# harger_for_auto_2.net
KiCad netlist of a schematic drawn in Altium Designer
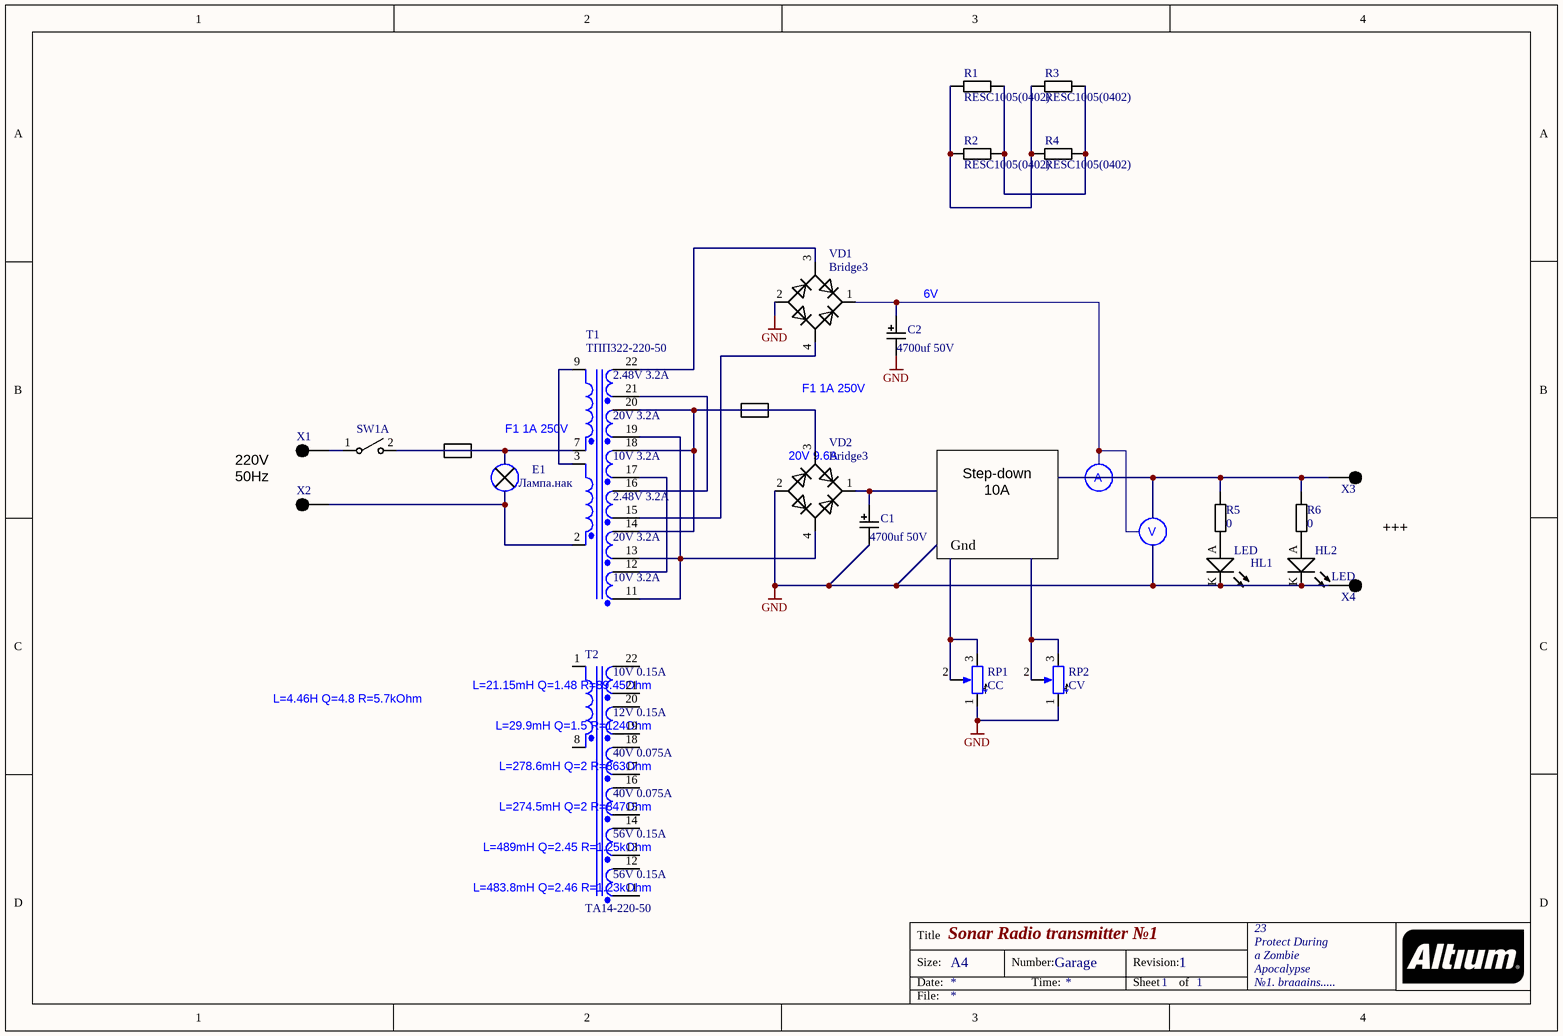
[diagram p0: Сharger for auto (2).SchDoc]

(export (version "E")
  (design (tool "Eeschema 10.0.6"))
  (components
    (comp (ref "C1")
      (value "4700uf 50V")
      (footprint "CAPMP3528X210N")
      (description "?")
      (fields (field (name "PART NUMBER") "CapTantB") (field (name "DIGI-KEY PART NUMBER") "478-5801-1-ND"))
      (libsource (lib "SssAccesDatbase") (part "Cap Pol1"))
    )
    (comp (ref "C2")
      (value "4700uf 50V")
      (footprint "CAPMP3528X210N")
      (description "?")
      (fields (field (name "PART NUMBER") "CapTantB") (field (name "DIGI-KEY PART NUMBER") "478-5801-1-ND"))
      (libsource (lib "SssAccesDatbase") (part "Cap Pol1"))
    )
    (comp (ref "E1") (value "Лампа.нак") (libsource (lib "SssAccesDatbase") (part "Лампа.нак")))
    (comp (ref "HL1")
      (value "LED")
      (footprint "LED 5mm Green")
      (description "?")
      (fields (field (name "PART NUMBER") "FYL-5013 GD"))
      (libsource (lib "SssAccesDatbase") (part "LED"))
    )
    (comp (ref "HL2")
      (value "LED")
      (footprint "LED 5mm Green")
      (description "?")
      (fields (field (name "PART NUMBER") "FYL-5013 GD"))
      (libsource (lib "SssAccesDatbase") (part "LED"))
    )
    (comp (ref "R1")
      (value "RESC1005(0402)")
      (footprint "REZKemet 0402")
      (fields (field (name "DIGI-KEY PART NUMBER") "???"))
      (libsource (lib "") (part "Resistor general_1"))
    )
    (comp (ref "R2")
      (value "RESC1005(0402)")
      (footprint "REZKemet 0402")
      (fields (field (name "DIGI-KEY PART NUMBER") "???"))
      (libsource (lib "") (part "Resistor general_1"))
    )
    (comp (ref "R3")
      (value "RESC1005(0402)")
      (footprint "REZKemet 0402")
      (fields (field (name "DIGI-KEY PART NUMBER") "???"))
      (libsource (lib "") (part "Resistor general_1"))
    )
    (comp (ref "R4")
      (value "RESC1005(0402)")
      (footprint "REZKemet 0402")
      (fields (field (name "DIGI-KEY PART NUMBER") "???"))
      (libsource (lib "") (part "Resistor general_1"))
    )
    (comp (ref "R5")
      (value "0")
      (footprint "REZKemet 0402")
      (fields (field (name "PART NUMBER") "RESC1005(0402)") (field (name "DIGI-KEY PART NUMBER") "???"))
      (libsource (lib "SssAccesDatbase") (part "Resistor general"))
    )
    (comp (ref "R6")
      (value "0")
      (footprint "REZKemet 0402")
      (fields (field (name "PART NUMBER") "RESC1005(0402)") (field (name "DIGI-KEY PART NUMBER") "???"))
      (libsource (lib "SssAccesDatbase") (part "Resistor general"))
    )
    (comp (ref "RP1")
      (value "CC")
      (footprint "POT16K1-LIN")
      (fields (field (name "PART NUMBER") "50k POT16K1-LIN") (field (name "DIGI-KEY PART NUMBER") "???"))
      (libsource (lib "SssAccesDatbase") (part "Pot"))
    )
    (comp (ref "RP2")
      (value "CV")
      (footprint "POT16K1-LIN")
      (fields (field (name "PART NUMBER") "50k POT16K1-LIN") (field (name "DIGI-KEY PART NUMBER") "???"))
      (libsource (lib "SssAccesDatbase") (part "Pot"))
    )
    (comp (ref "SW1")
      (value "219-12MST")
      (footprint "219-12MST")
      (description "SWITCH SLIDE DIP SPST 100MA 20V")
      (fields (field (name "DIGI-KEY PART NUMBER") "CT21912MST-ND"))
      (libsource (lib "SssAccesDatbase") (part "SW-DIP_12"))
    )
    (comp (ref "T1")
      (value "ТПП322-220-50")
      (fields (field (name "PUBLISHER") "Altium Limited"))
      (libsource (lib "SssAccesDatbase") (part "ТПП322-220-50"))
    )
    (comp (ref "T2")
      (value "ТА14-220-50")
      (fields (field (name "PUBLISHER") "Altium Limited"))
      (libsource (lib "SssAccesDatbase") (part "ТА14-220-50"))
    )
    (comp (ref "VD1")
      (value "Bridge3")
      (footprint "DF206ST-G")
      (description "Miniature Glass Passivated Single-Phase\r\nSurface Mount Bridge Rectifiers")
      (fields (field (name "PART NUMBER") "DF10S-E3/77") (field (name "MANUFACTURER PART NUMBER") "?"))
      (libsource (lib "SssAccesDatbase") (part "Bridge3"))
    )
    (comp (ref "VD2")
      (value "Bridge3")
      (footprint "DF206ST-G")
      (description "Miniature Glass Passivated Single-Phase\r\nSurface Mount Bridge Rectifiers")
      (fields (field (name "PART NUMBER") "DF10S-E3/77") (field (name "MANUFACTURER PART NUMBER") "?"))
      (libsource (lib "SssAccesDatbase") (part "Bridge3"))
    )
    (comp (ref "X1")
      (value "X1-PLS-1")
      (footprint "HoleSolderPLS-1")
      (description "контакт под пайку")
      (libsource (lib "SssAccesDatbase") (part "X1_1"))
    )
    (comp (ref "X2")
      (value "X1-PLS-1")
      (footprint "HoleSolderPLS-1")
      (description "контакт под пайку")
      (libsource (lib "SssAccesDatbase") (part "X1_1"))
    )
    (comp (ref "X3")
      (value "X1-PLS-1")
      (footprint "HoleSolderPLS-1")
      (description "контакт под пайку")
      (libsource (lib "SssAccesDatbase") (part "X1_1"))
    )
    (comp (ref "X4")
      (value "X1-PLS-1")
      (footprint "HoleSolderPLS-1")
      (description "контакт под пайку")
      (libsource (lib "SssAccesDatbase") (part "X1_1"))
    )
  )
  (nets
    (net (code "1") (name "GND") (class "Default")
      (node (ref "C1") (pin "2") (pinfunction "2_2") (pintype "passive"))
      (node (ref "C2") (pin "2") (pinfunction "2_2") (pintype "passive"))
      (node (ref "HL1") (pin "K") (pinfunction "K_K") (pintype "passive"))
      (node (ref "HL2") (pin "K") (pinfunction "K_K") (pintype "passive"))
      (node (ref "RP1") (pin "1") (pinfunction "TOP_1") (pintype "passive"))
      (node (ref "RP2") (pin "1") (pinfunction "TOP_1") (pintype "passive"))
      (node (ref "VD1") (pin "2") (pinfunction "A_2") (pintype "passive"))
      (node (ref "VD2") (pin "2") (pinfunction "A_2") (pintype "passive"))
      (node (ref "X4") (pin "1") (pinfunction "1_1") (pintype "passive"))
    )
    (net (code "2") (name "Net-(C1-Pad1)") (class "Default")
      (node (ref "C1") (pin "1") (pinfunction "1_1") (pintype "passive"))
      (node (ref "VD2") (pin "1") (pinfunction "C_1") (pintype "passive"))
    )
    (net (code "3") (name "Net-(C2-Pad1)") (class "Default")
      (node (ref "C2") (pin "1") (pinfunction "1_1") (pintype "passive"))
      (node (ref "VD1") (pin "1") (pinfunction "C_1") (pintype "passive"))
    )
    (net (code "4") (name "Net-(HL1-PadA)") (class "Default")
      (node (ref "HL1") (pin "A") (pinfunction "A_A") (pintype "passive"))
      (node (ref "R5") (pin "1") (pinfunction "1_1") (pintype "passive"))
    )
    (net (code "5") (name "Net-(HL2-PadA)") (class "Default")
      (node (ref "HL2") (pin "A") (pinfunction "A_A") (pintype "passive"))
      (node (ref "R6") (pin "1") (pinfunction "1_1") (pintype "passive"))
    )
    (net (code "6") (name "Net-(R1-Pad1)") (class "Default")
      (node (ref "R1") (pin "1") (pinfunction "1_1") (pintype "passive"))
      (node (ref "R2") (pin "1") (pinfunction "1_1") (pintype "passive"))
      (node (ref "R3") (pin "1") (pinfunction "1_1") (pintype "passive"))
      (node (ref "R4") (pin "1") (pinfunction "1_1") (pintype "passive"))
    )
    (net (code "7") (name "Net-(R1-Pad2)") (class "Default")
      (node (ref "R1") (pin "2") (pinfunction "2_2") (pintype "passive"))
      (node (ref "R2") (pin "2") (pinfunction "2_2") (pintype "passive"))
      (node (ref "R3") (pin "2") (pinfunction "2_2") (pintype "passive"))
      (node (ref "R4") (pin "2") (pinfunction "2_2") (pintype "passive"))
    )
    (net (code "8") (name "Net-(R5-Pad2)") (class "Default")
      (node (ref "R5") (pin "2") (pinfunction "2_2") (pintype "passive"))
      (node (ref "R6") (pin "2") (pinfunction "2_2") (pintype "passive"))
      (node (ref "X3") (pin "1") (pinfunction "1_1") (pintype "passive"))
    )
    (net (code "9") (name "Net-(RP1-BOT)") (class "Default")
      (node (ref "RP1") (pin "2") (pinfunction "BOT_2") (pintype "passive"))
      (node (ref "RP1") (pin "3") (pinfunction "TAP_3") (pintype "passive"))
    )
    (net (code "10") (name "Net-(RP2-BOT)") (class "Default")
      (node (ref "RP2") (pin "2") (pinfunction "BOT_2") (pintype "passive"))
      (node (ref "RP2") (pin "3") (pinfunction "TAP_3") (pintype "passive"))
    )
    (net (code "11") (name "Net-(SW1-Pad1)") (class "Default")
      (node (ref "SW1") (pin "1") (pinfunction "1_1") (pintype "passive"))
      (node (ref "X1") (pin "1") (pinfunction "1_1") (pintype "passive"))
    )
    (net (code "12") (name "Net-(T1-Pri1+)") (class "Default")
      (node (ref "T1") (pin "2") (pinfunction "Pri1+_2") (pintype "passive"))
      (node (ref "X2") (pin "1") (pinfunction "1_1") (pintype "passive"))
    )
    (net (code "13") (name "Net-(T1-Pri1-)") (class "Default")
      (node (ref "T1") (pin "3") (pinfunction "Pri1-_3") (pintype "passive"))
      (node (ref "T1") (pin "9") (pinfunction "Pri2-_9") (pintype "passive"))
    )
    (net (code "14") (name "Net-(T1-Pri2+)") (class "Default")
      (node (ref "SW1") (pin "2") (pinfunction "2_2") (pintype "passive"))
      (node (ref "T1") (pin "7") (pinfunction "Pri2+_7") (pintype "passive"))
    )
    (net (code "15") (name "Net-(T1-Sec2+-Pad11)") (class "Default")
      (node (ref "T1") (pin "11") (pinfunction "Sec2+_11") (pintype "passive"))
      (node (ref "T1") (pin "13") (pinfunction "Sec2+_13") (pintype "passive"))
      (node (ref "T1") (pin "19") (pinfunction "Sec2+_19") (pintype "passive"))
      (node (ref "VD2") (pin "4") (pinfunction "C_4") (pintype "passive"))
    )
    (net (code "16") (name "Net-(T1-Sec2+-Pad15)") (class "Default")
      (node (ref "T1") (pin "15") (pinfunction "Sec2+_15") (pintype "passive"))
      (node (ref "VD1") (pin "4") (pinfunction "C_4") (pintype "passive"))
    )
    (net (code "17") (name "Net-(T1-Sec2+-Pad17)") (class "Default")
      (node (ref "T1") (pin "12") (pinfunction "Sec2-_12") (pintype "passive"))
      (node (ref "T1") (pin "17") (pinfunction "Sec2+_17") (pintype "passive"))
    )
    (net (code "18") (name "Net-(T1-Sec2+-Pad21)") (class "Default")
      (node (ref "T1") (pin "16") (pinfunction "Sec2-_16") (pintype "passive"))
      (node (ref "T1") (pin "21") (pinfunction "Sec2+_21") (pintype "passive"))
    )
    (net (code "19") (name "Net-(T1-Sec2--Pad14)") (class "Default")
      (node (ref "T1") (pin "14") (pinfunction "Sec2-_14") (pintype "passive"))
      (node (ref "T1") (pin "18") (pinfunction "Sec2-_18") (pintype "passive"))
      (node (ref "T1") (pin "20") (pinfunction "Sec2-_20") (pintype "passive"))
      (node (ref "VD2") (pin "3") (pinfunction "C_3") (pintype "passive"))
    )
    (net (code "20") (name "Net-(T1-Sec2--Pad22)") (class "Default")
      (node (ref "T1") (pin "22") (pinfunction "Sec2-_22") (pintype "passive"))
      (node (ref "VD1") (pin "3") (pinfunction "C_3") (pintype "passive"))
    )
    (net (code "21") (name "unconnected-(T2-Pri2+-Pad8)") (class "Default")
      (node (ref "T2") (pin "8") (pinfunction "Pri2+_8") (pintype "passive"))
    )
    (net (code "22") (name "unconnected-(T2-Pri2--Pad1)") (class "Default")
      (node (ref "T2") (pin "1") (pinfunction "Pri2-_1") (pintype "passive"))
    )
    (net (code "23") (name "unconnected-(T2-Sec2+-Pad11)") (class "Default")
      (node (ref "T2") (pin "11") (pinfunction "Sec2+_11") (pintype "passive"))
    )
    (net (code "24") (name "unconnected-(T2-Sec2+-Pad13)") (class "Default")
      (node (ref "T2") (pin "13") (pinfunction "Sec2+_13") (pintype "passive"))
    )
    (net (code "25") (name "unconnected-(T2-Sec2+-Pad15)") (class "Default")
      (node (ref "T2") (pin "15") (pinfunction "Sec2+_15") (pintype "passive"))
    )
    (net (code "26") (name "unconnected-(T2-Sec2+-Pad17)") (class "Default")
      (node (ref "T2") (pin "17") (pinfunction "Sec2+_17") (pintype "passive"))
    )
    (net (code "27") (name "unconnected-(T2-Sec2+-Pad19)") (class "Default")
      (node (ref "T2") (pin "19") (pinfunction "Sec2+_19") (pintype "passive"))
    )
    (net (code "28") (name "unconnected-(T2-Sec2+-Pad21)") (class "Default")
      (node (ref "T2") (pin "21") (pinfunction "Sec2+_21") (pintype "passive"))
    )
    (net (code "29") (name "unconnected-(T2-Sec2--Pad12)") (class "Default")
      (node (ref "T2") (pin "12") (pinfunction "Sec2-_12") (pintype "passive"))
    )
    (net (code "30") (name "unconnected-(T2-Sec2--Pad14)") (class "Default")
      (node (ref "T2") (pin "14") (pinfunction "Sec2-_14") (pintype "passive"))
    )
    (net (code "31") (name "unconnected-(T2-Sec2--Pad16)") (class "Default")
      (node (ref "T2") (pin "16") (pinfunction "Sec2-_16") (pintype "passive"))
    )
    (net (code "32") (name "unconnected-(T2-Sec2--Pad18)") (class "Default")
      (node (ref "T2") (pin "18") (pinfunction "Sec2-_18") (pintype "passive"))
    )
    (net (code "33") (name "unconnected-(T2-Sec2--Pad20)") (class "Default")
      (node (ref "T2") (pin "20") (pinfunction "Sec2-_20") (pintype "passive"))
    )
    (net (code "34") (name "unconnected-(T2-Sec2--Pad22)") (class "Default")
      (node (ref "T2") (pin "22") (pinfunction "Sec2-_22") (pintype "passive"))
    )
  )
)
